# proto.net
KiCad netlist of a schematic drawn in EAGLE
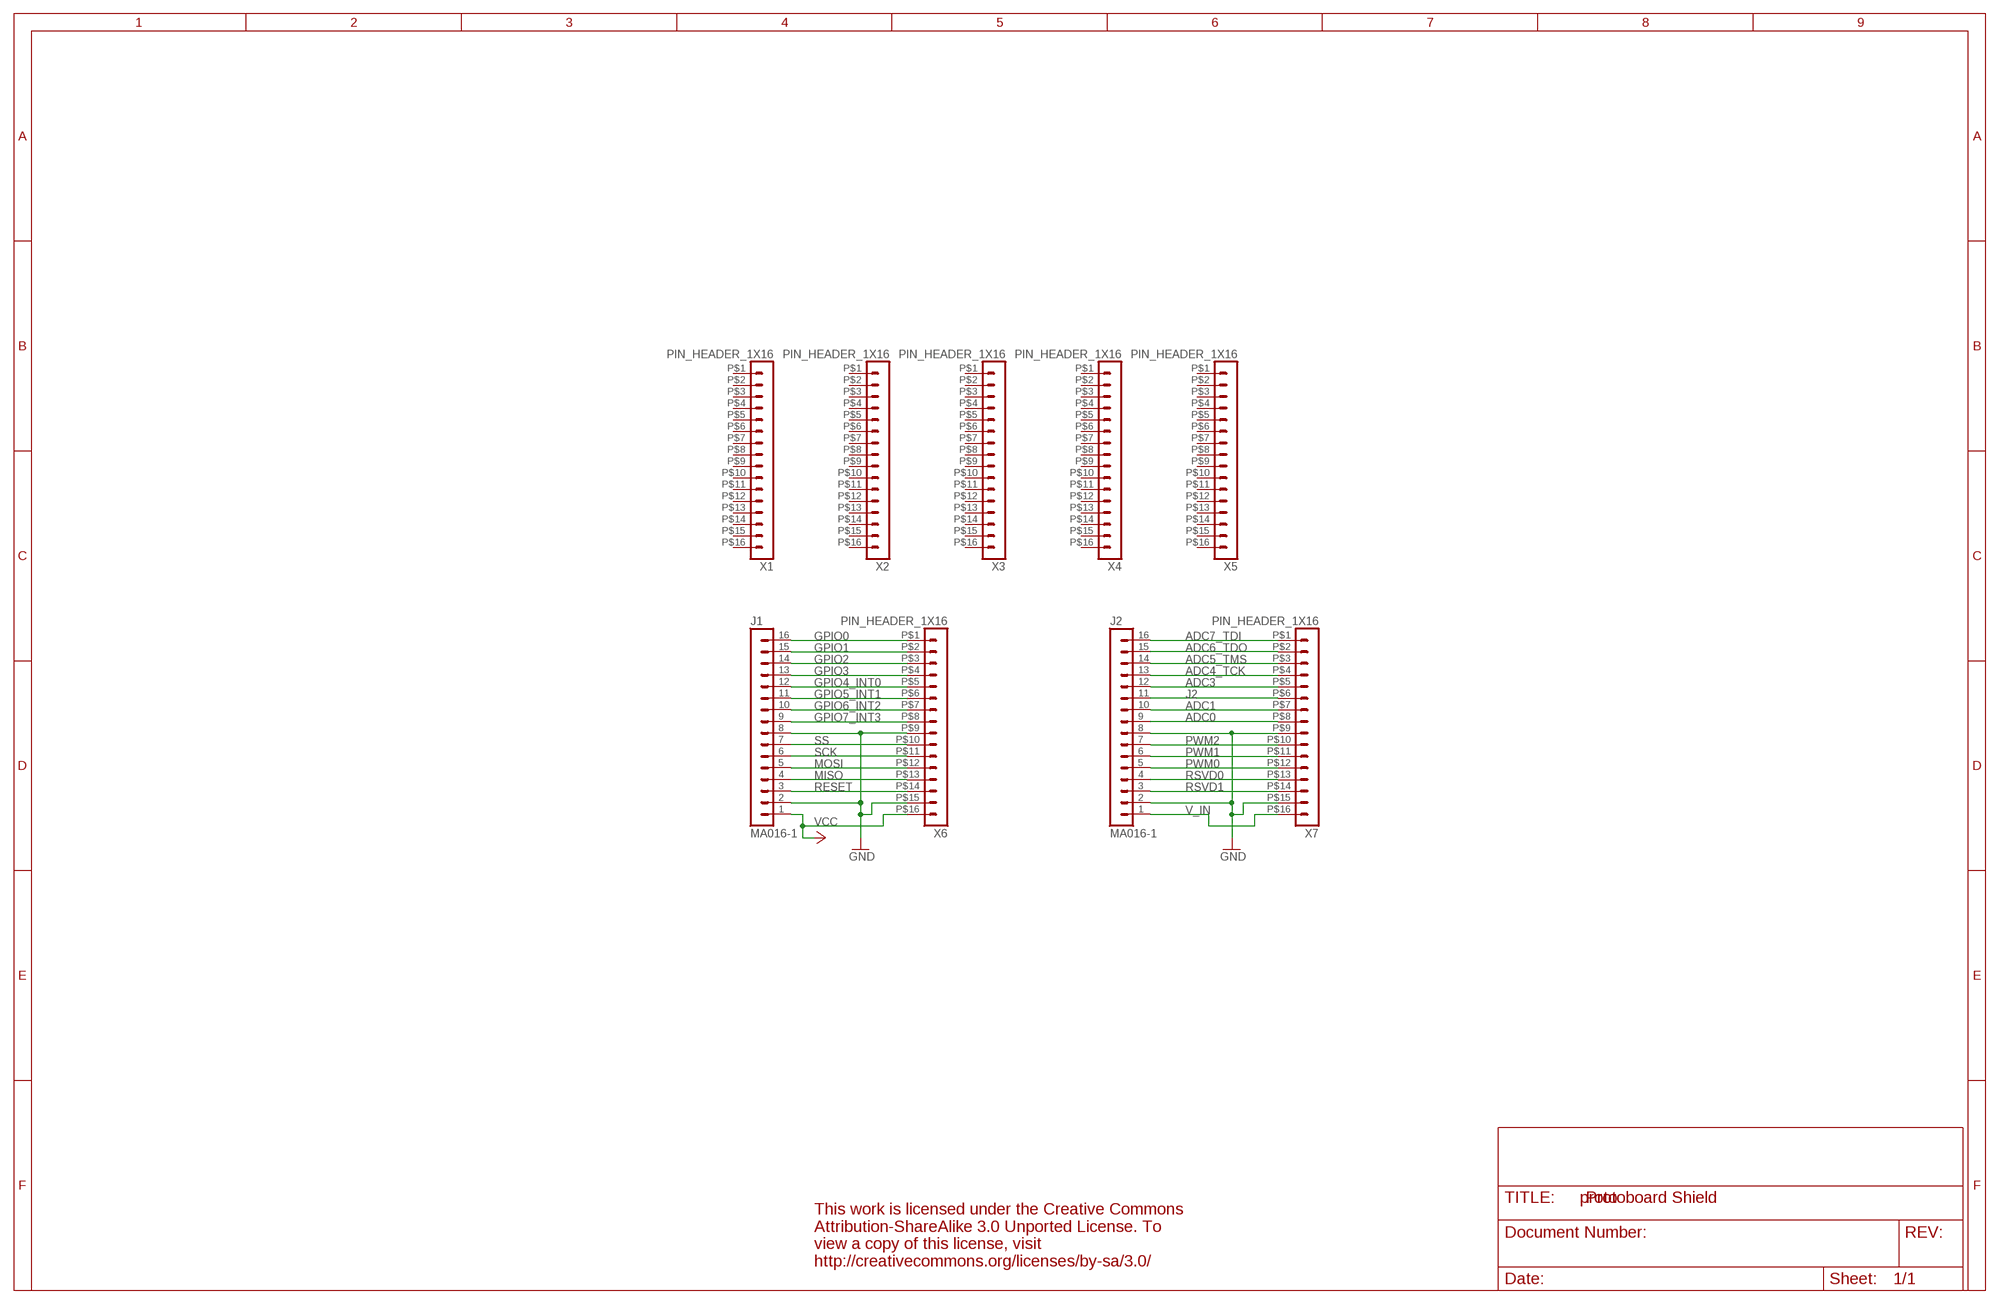
[diagram p0: schematic, sheet 1]

(export (version "E")
  (design (tool "Eeschema 10.0.6"))
  (components
    (comp (ref "J1")
      (value "MA016-1")
      (footprint "eagle-import:MA016-1")
      (libsource (lib "eagle-import") (part "MA016-1"))
    )
    (comp (ref "J2")
      (value "MA016-1")
      (footprint "eagle-import:MA016-1")
      (libsource (lib "eagle-import") (part "MA016-1"))
    )
    (comp (ref "X1")
      (value "PIN_HEADER_1X16")
      (footprint "eagle-import:PIN_HEADER_1X16")
      (libsource (lib "eagle-import") (part "PIN_HEADER_1X16"))
    )
    (comp (ref "X2")
      (value "PIN_HEADER_1X16")
      (footprint "eagle-import:PIN_HEADER_1X16")
      (libsource (lib "eagle-import") (part "PIN_HEADER_1X16"))
    )
    (comp (ref "X3")
      (value "PIN_HEADER_1X16")
      (footprint "eagle-import:PIN_HEADER_1X16")
      (libsource (lib "eagle-import") (part "PIN_HEADER_1X16"))
    )
    (comp (ref "X4")
      (value "PIN_HEADER_1X16")
      (footprint "eagle-import:PIN_HEADER_1X16")
      (libsource (lib "eagle-import") (part "PIN_HEADER_1X16"))
    )
    (comp (ref "X5")
      (value "PIN_HEADER_1X16")
      (footprint "eagle-import:PIN_HEADER_1X16")
      (libsource (lib "eagle-import") (part "PIN_HEADER_1X16"))
    )
    (comp (ref "X6")
      (value "PIN_HEADER_1X16")
      (footprint "eagle-import:PIN_HEADER_1X16")
      (libsource (lib "eagle-import") (part "PIN_HEADER_1X16"))
    )
    (comp (ref "X7")
      (value "PIN_HEADER_1X16")
      (footprint "eagle-import:PIN_HEADER_1X16")
      (libsource (lib "eagle-import") (part "PIN_HEADER_1X16"))
    )
  )
  (nets
    (net (code "1") (name "/ADC0") (class "Default")
      (node (ref "J2") (pin "9") (pinfunction "9_9") (pintype "passive"))
      (node (ref "X7") (pin "P$8") (pinfunction "8_P$8") (pintype "passive"))
    )
    (net (code "2") (name "/ADC1") (class "Default")
      (node (ref "J2") (pin "10") (pinfunction "10_10") (pintype "passive"))
      (node (ref "X7") (pin "P$7") (pinfunction "7_P$7") (pintype "passive"))
    )
    (net (code "3") (name "/ADC3") (class "Default")
      (node (ref "J2") (pin "12") (pinfunction "12_12") (pintype "passive"))
      (node (ref "X7") (pin "P$5") (pinfunction "5_P$5") (pintype "passive"))
    )
    (net (code "4") (name "/ADC4_TCK") (class "Default")
      (node (ref "J2") (pin "13") (pinfunction "13_13") (pintype "passive"))
      (node (ref "X7") (pin "P$4") (pinfunction "4_P$4") (pintype "passive"))
    )
    (net (code "5") (name "/ADC5_TMS") (class "Default")
      (node (ref "J2") (pin "14") (pinfunction "14_14") (pintype "passive"))
      (node (ref "X7") (pin "P$3") (pinfunction "3_P$3") (pintype "passive"))
    )
    (net (code "6") (name "/ADC6_TDO") (class "Default")
      (node (ref "J2") (pin "15") (pinfunction "15_15") (pintype "passive"))
      (node (ref "X7") (pin "P$2") (pinfunction "2_P$2") (pintype "passive"))
    )
    (net (code "7") (name "/ADC7_TDI") (class "Default")
      (node (ref "J2") (pin "16") (pinfunction "16_16") (pintype "passive"))
      (node (ref "X7") (pin "P$1") (pinfunction "1_P$1") (pintype "passive"))
    )
    (net (code "8") (name "/GPIO0") (class "Default")
      (node (ref "J1") (pin "16") (pinfunction "16_16") (pintype "passive"))
      (node (ref "X6") (pin "P$1") (pinfunction "1_P$1") (pintype "passive"))
    )
    (net (code "9") (name "/GPIO1") (class "Default")
      (node (ref "J1") (pin "15") (pinfunction "15_15") (pintype "passive"))
      (node (ref "X6") (pin "P$2") (pinfunction "2_P$2") (pintype "passive"))
    )
    (net (code "10") (name "/GPIO2") (class "Default")
      (node (ref "J1") (pin "14") (pinfunction "14_14") (pintype "passive"))
      (node (ref "X6") (pin "P$3") (pinfunction "3_P$3") (pintype "passive"))
    )
    (net (code "11") (name "/GPIO3") (class "Default")
      (node (ref "J1") (pin "13") (pinfunction "13_13") (pintype "passive"))
      (node (ref "X6") (pin "P$4") (pinfunction "4_P$4") (pintype "passive"))
    )
    (net (code "12") (name "/GPIO4_INT0") (class "Default")
      (node (ref "J1") (pin "12") (pinfunction "12_12") (pintype "passive"))
      (node (ref "X6") (pin "P$5") (pinfunction "5_P$5") (pintype "passive"))
    )
    (net (code "13") (name "/GPIO5_INT1") (class "Default")
      (node (ref "J1") (pin "11") (pinfunction "11_11") (pintype "passive"))
      (node (ref "X6") (pin "P$6") (pinfunction "6_P$6") (pintype "passive"))
    )
    (net (code "14") (name "/GPIO6_INT2") (class "Default")
      (node (ref "J1") (pin "10") (pinfunction "10_10") (pintype "passive"))
      (node (ref "X6") (pin "P$7") (pinfunction "7_P$7") (pintype "passive"))
    )
    (net (code "15") (name "/GPIO7_INT3") (class "Default")
      (node (ref "J1") (pin "9") (pinfunction "9_9") (pintype "passive"))
      (node (ref "X6") (pin "P$8") (pinfunction "8_P$8") (pintype "passive"))
    )
    (net (code "16") (name "/J2") (class "Default")
      (node (ref "J2") (pin "11") (pinfunction "11_11") (pintype "passive"))
      (node (ref "X7") (pin "P$6") (pinfunction "6_P$6") (pintype "passive"))
    )
    (net (code "17") (name "/MISO") (class "Default")
      (node (ref "J1") (pin "4") (pinfunction "4_4") (pintype "passive"))
      (node (ref "X6") (pin "P$13") (pinfunction "13_P$13") (pintype "passive"))
    )
    (net (code "18") (name "/MOSI") (class "Default")
      (node (ref "J1") (pin "5") (pinfunction "5_5") (pintype "passive"))
      (node (ref "X6") (pin "P$12") (pinfunction "12_P$12") (pintype "passive"))
    )
    (net (code "19") (name "/PWM0") (class "Default")
      (node (ref "J2") (pin "5") (pinfunction "5_5") (pintype "passive"))
      (node (ref "X7") (pin "P$12") (pinfunction "12_P$12") (pintype "passive"))
    )
    (net (code "20") (name "/PWM1") (class "Default")
      (node (ref "J2") (pin "6") (pinfunction "6_6") (pintype "passive"))
      (node (ref "X7") (pin "P$11") (pinfunction "11_P$11") (pintype "passive"))
    )
    (net (code "21") (name "/PWM2") (class "Default")
      (node (ref "J2") (pin "7") (pinfunction "7_7") (pintype "passive"))
      (node (ref "X7") (pin "P$10") (pinfunction "10_P$10") (pintype "passive"))
    )
    (net (code "22") (name "/RESET") (class "Default")
      (node (ref "J1") (pin "3") (pinfunction "3_3") (pintype "passive"))
      (node (ref "X6") (pin "P$14") (pinfunction "14_P$14") (pintype "passive"))
    )
    (net (code "23") (name "/RSVD0") (class "Default")
      (node (ref "J2") (pin "4") (pinfunction "4_4") (pintype "passive"))
      (node (ref "X7") (pin "P$13") (pinfunction "13_P$13") (pintype "passive"))
    )
    (net (code "24") (name "/RSVD1") (class "Default")
      (node (ref "J2") (pin "3") (pinfunction "3_3") (pintype "passive"))
      (node (ref "X7") (pin "P$14") (pinfunction "14_P$14") (pintype "passive"))
    )
    (net (code "25") (name "/SCK") (class "Default")
      (node (ref "J1") (pin "6") (pinfunction "6_6") (pintype "passive"))
      (node (ref "X6") (pin "P$11") (pinfunction "11_P$11") (pintype "passive"))
    )
    (net (code "26") (name "/SS") (class "Default")
      (node (ref "J1") (pin "7") (pinfunction "7_7") (pintype "passive"))
      (node (ref "X6") (pin "P$10") (pinfunction "10_P$10") (pintype "passive"))
    )
    (net (code "27") (name "/V_IN") (class "Default")
      (node (ref "J2") (pin "1") (pinfunction "1_1") (pintype "passive"))
      (node (ref "X7") (pin "P$16") (pinfunction "16_P$16") (pintype "passive"))
    )
    (net (code "28") (name "GND") (class "Default")
      (node (ref "J1") (pin "2") (pinfunction "2_2") (pintype "passive"))
      (node (ref "J1") (pin "8") (pinfunction "8_8") (pintype "passive"))
      (node (ref "J2") (pin "2") (pinfunction "2_2") (pintype "passive"))
      (node (ref "J2") (pin "8") (pinfunction "8_8") (pintype "passive"))
      (node (ref "X6") (pin "P$15") (pinfunction "15_P$15") (pintype "passive"))
      (node (ref "X6") (pin "P$9") (pinfunction "9_P$9") (pintype "passive"))
      (node (ref "X7") (pin "P$15") (pinfunction "15_P$15") (pintype "passive"))
      (node (ref "X7") (pin "P$9") (pinfunction "9_P$9") (pintype "passive"))
    )
    (net (code "29") (name "VCC") (class "Default")
      (node (ref "J1") (pin "1") (pinfunction "1_1") (pintype "passive"))
      (node (ref "X6") (pin "P$16") (pinfunction "16_P$16") (pintype "passive"))
    )
    (net (code "30") (name "unconnected-(X1-1-PadP$1)") (class "Default")
      (node (ref "X1") (pin "P$1") (pinfunction "1_P$1") (pintype "passive"))
    )
    (net (code "31") (name "unconnected-(X1-2-PadP$2)") (class "Default")
      (node (ref "X1") (pin "P$2") (pinfunction "2_P$2") (pintype "passive"))
    )
    (net (code "32") (name "unconnected-(X1-3-PadP$3)") (class "Default")
      (node (ref "X1") (pin "P$3") (pinfunction "3_P$3") (pintype "passive"))
    )
    (net (code "33") (name "unconnected-(X1-4-PadP$4)") (class "Default")
      (node (ref "X1") (pin "P$4") (pinfunction "4_P$4") (pintype "passive"))
    )
    (net (code "34") (name "unconnected-(X1-5-PadP$5)") (class "Default")
      (node (ref "X1") (pin "P$5") (pinfunction "5_P$5") (pintype "passive"))
    )
    (net (code "35") (name "unconnected-(X1-6-PadP$6)") (class "Default")
      (node (ref "X1") (pin "P$6") (pinfunction "6_P$6") (pintype "passive"))
    )
    (net (code "36") (name "unconnected-(X1-7-PadP$7)") (class "Default")
      (node (ref "X1") (pin "P$7") (pinfunction "7_P$7") (pintype "passive"))
    )
    (net (code "37") (name "unconnected-(X1-8-PadP$8)") (class "Default")
      (node (ref "X1") (pin "P$8") (pinfunction "8_P$8") (pintype "passive"))
    )
    (net (code "38") (name "unconnected-(X1-9-PadP$9)") (class "Default")
      (node (ref "X1") (pin "P$9") (pinfunction "9_P$9") (pintype "passive"))
    )
    (net (code "39") (name "unconnected-(X1-10-PadP$10)") (class "Default")
      (node (ref "X1") (pin "P$10") (pinfunction "10_P$10") (pintype "passive"))
    )
    (net (code "40") (name "unconnected-(X1-11-PadP$11)") (class "Default")
      (node (ref "X1") (pin "P$11") (pinfunction "11_P$11") (pintype "passive"))
    )
    (net (code "41") (name "unconnected-(X1-12-PadP$12)") (class "Default")
      (node (ref "X1") (pin "P$12") (pinfunction "12_P$12") (pintype "passive"))
    )
    (net (code "42") (name "unconnected-(X1-13-PadP$13)") (class "Default")
      (node (ref "X1") (pin "P$13") (pinfunction "13_P$13") (pintype "passive"))
    )
    (net (code "43") (name "unconnected-(X1-14-PadP$14)") (class "Default")
      (node (ref "X1") (pin "P$14") (pinfunction "14_P$14") (pintype "passive"))
    )
    (net (code "44") (name "unconnected-(X1-15-PadP$15)") (class "Default")
      (node (ref "X1") (pin "P$15") (pinfunction "15_P$15") (pintype "passive"))
    )
    (net (code "45") (name "unconnected-(X1-16-PadP$16)") (class "Default")
      (node (ref "X1") (pin "P$16") (pinfunction "16_P$16") (pintype "passive"))
    )
    (net (code "46") (name "unconnected-(X2-1-PadP$1)") (class "Default")
      (node (ref "X2") (pin "P$1") (pinfunction "1_P$1") (pintype "passive"))
    )
    (net (code "47") (name "unconnected-(X2-2-PadP$2)") (class "Default")
      (node (ref "X2") (pin "P$2") (pinfunction "2_P$2") (pintype "passive"))
    )
    (net (code "48") (name "unconnected-(X2-3-PadP$3)") (class "Default")
      (node (ref "X2") (pin "P$3") (pinfunction "3_P$3") (pintype "passive"))
    )
    (net (code "49") (name "unconnected-(X2-4-PadP$4)") (class "Default")
      (node (ref "X2") (pin "P$4") (pinfunction "4_P$4") (pintype "passive"))
    )
    (net (code "50") (name "unconnected-(X2-5-PadP$5)") (class "Default")
      (node (ref "X2") (pin "P$5") (pinfunction "5_P$5") (pintype "passive"))
    )
    (net (code "51") (name "unconnected-(X2-6-PadP$6)") (class "Default")
      (node (ref "X2") (pin "P$6") (pinfunction "6_P$6") (pintype "passive"))
    )
    (net (code "52") (name "unconnected-(X2-7-PadP$7)") (class "Default")
      (node (ref "X2") (pin "P$7") (pinfunction "7_P$7") (pintype "passive"))
    )
    (net (code "53") (name "unconnected-(X2-8-PadP$8)") (class "Default")
      (node (ref "X2") (pin "P$8") (pinfunction "8_P$8") (pintype "passive"))
    )
    (net (code "54") (name "unconnected-(X2-9-PadP$9)") (class "Default")
      (node (ref "X2") (pin "P$9") (pinfunction "9_P$9") (pintype "passive"))
    )
    (net (code "55") (name "unconnected-(X2-10-PadP$10)") (class "Default")
      (node (ref "X2") (pin "P$10") (pinfunction "10_P$10") (pintype "passive"))
    )
    (net (code "56") (name "unconnected-(X2-11-PadP$11)") (class "Default")
      (node (ref "X2") (pin "P$11") (pinfunction "11_P$11") (pintype "passive"))
    )
    (net (code "57") (name "unconnected-(X2-12-PadP$12)") (class "Default")
      (node (ref "X2") (pin "P$12") (pinfunction "12_P$12") (pintype "passive"))
    )
    (net (code "58") (name "unconnected-(X2-13-PadP$13)") (class "Default")
      (node (ref "X2") (pin "P$13") (pinfunction "13_P$13") (pintype "passive"))
    )
    (net (code "59") (name "unconnected-(X2-14-PadP$14)") (class "Default")
      (node (ref "X2") (pin "P$14") (pinfunction "14_P$14") (pintype "passive"))
    )
    (net (code "60") (name "unconnected-(X2-15-PadP$15)") (class "Default")
      (node (ref "X2") (pin "P$15") (pinfunction "15_P$15") (pintype "passive"))
    )
    (net (code "61") (name "unconnected-(X2-16-PadP$16)") (class "Default")
      (node (ref "X2") (pin "P$16") (pinfunction "16_P$16") (pintype "passive"))
    )
    (net (code "62") (name "unconnected-(X3-1-PadP$1)") (class "Default")
      (node (ref "X3") (pin "P$1") (pinfunction "1_P$1") (pintype "passive"))
    )
    (net (code "63") (name "unconnected-(X3-2-PadP$2)") (class "Default")
      (node (ref "X3") (pin "P$2") (pinfunction "2_P$2") (pintype "passive"))
    )
    (net (code "64") (name "unconnected-(X3-3-PadP$3)") (class "Default")
      (node (ref "X3") (pin "P$3") (pinfunction "3_P$3") (pintype "passive"))
    )
    (net (code "65") (name "unconnected-(X3-4-PadP$4)") (class "Default")
      (node (ref "X3") (pin "P$4") (pinfunction "4_P$4") (pintype "passive"))
    )
    (net (code "66") (name "unconnected-(X3-5-PadP$5)") (class "Default")
      (node (ref "X3") (pin "P$5") (pinfunction "5_P$5") (pintype "passive"))
    )
    (net (code "67") (name "unconnected-(X3-6-PadP$6)") (class "Default")
      (node (ref "X3") (pin "P$6") (pinfunction "6_P$6") (pintype "passive"))
    )
    (net (code "68") (name "unconnected-(X3-7-PadP$7)") (class "Default")
      (node (ref "X3") (pin "P$7") (pinfunction "7_P$7") (pintype "passive"))
    )
    (net (code "69") (name "unconnected-(X3-8-PadP$8)") (class "Default")
      (node (ref "X3") (pin "P$8") (pinfunction "8_P$8") (pintype "passive"))
    )
    (net (code "70") (name "unconnected-(X3-9-PadP$9)") (class "Default")
      (node (ref "X3") (pin "P$9") (pinfunction "9_P$9") (pintype "passive"))
    )
    (net (code "71") (name "unconnected-(X3-10-PadP$10)") (class "Default")
      (node (ref "X3") (pin "P$10") (pinfunction "10_P$10") (pintype "passive"))
    )
    (net (code "72") (name "unconnected-(X3-11-PadP$11)") (class "Default")
      (node (ref "X3") (pin "P$11") (pinfunction "11_P$11") (pintype "passive"))
    )
    (net (code "73") (name "unconnected-(X3-12-PadP$12)") (class "Default")
      (node (ref "X3") (pin "P$12") (pinfunction "12_P$12") (pintype "passive"))
    )
    (net (code "74") (name "unconnected-(X3-13-PadP$13)") (class "Default")
      (node (ref "X3") (pin "P$13") (pinfunction "13_P$13") (pintype "passive"))
    )
    (net (code "75") (name "unconnected-(X3-14-PadP$14)") (class "Default")
      (node (ref "X3") (pin "P$14") (pinfunction "14_P$14") (pintype "passive"))
    )
    (net (code "76") (name "unconnected-(X3-15-PadP$15)") (class "Default")
      (node (ref "X3") (pin "P$15") (pinfunction "15_P$15") (pintype "passive"))
    )
    (net (code "77") (name "unconnected-(X3-16-PadP$16)") (class "Default")
      (node (ref "X3") (pin "P$16") (pinfunction "16_P$16") (pintype "passive"))
    )
    (net (code "78") (name "unconnected-(X4-1-PadP$1)") (class "Default")
      (node (ref "X4") (pin "P$1") (pinfunction "1_P$1") (pintype "passive"))
    )
    (net (code "79") (name "unconnected-(X4-2-PadP$2)") (class "Default")
      (node (ref "X4") (pin "P$2") (pinfunction "2_P$2") (pintype "passive"))
    )
    (net (code "80") (name "unconnected-(X4-3-PadP$3)") (class "Default")
      (node (ref "X4") (pin "P$3") (pinfunction "3_P$3") (pintype "passive"))
    )
    (net (code "81") (name "unconnected-(X4-4-PadP$4)") (class "Default")
      (node (ref "X4") (pin "P$4") (pinfunction "4_P$4") (pintype "passive"))
    )
    (net (code "82") (name "unconnected-(X4-5-PadP$5)") (class "Default")
      (node (ref "X4") (pin "P$5") (pinfunction "5_P$5") (pintype "passive"))
    )
    (net (code "83") (name "unconnected-(X4-6-PadP$6)") (class "Default")
      (node (ref "X4") (pin "P$6") (pinfunction "6_P$6") (pintype "passive"))
    )
    (net (code "84") (name "unconnected-(X4-7-PadP$7)") (class "Default")
      (node (ref "X4") (pin "P$7") (pinfunction "7_P$7") (pintype "passive"))
    )
    (net (code "85") (name "unconnected-(X4-8-PadP$8)") (class "Default")
      (node (ref "X4") (pin "P$8") (pinfunction "8_P$8") (pintype "passive"))
    )
    (net (code "86") (name "unconnected-(X4-9-PadP$9)") (class "Default")
      (node (ref "X4") (pin "P$9") (pinfunction "9_P$9") (pintype "passive"))
    )
    (net (code "87") (name "unconnected-(X4-10-PadP$10)") (class "Default")
      (node (ref "X4") (pin "P$10") (pinfunction "10_P$10") (pintype "passive"))
    )
    (net (code "88") (name "unconnected-(X4-11-PadP$11)") (class "Default")
      (node (ref "X4") (pin "P$11") (pinfunction "11_P$11") (pintype "passive"))
    )
    (net (code "89") (name "unconnected-(X4-12-PadP$12)") (class "Default")
      (node (ref "X4") (pin "P$12") (pinfunction "12_P$12") (pintype "passive"))
    )
    (net (code "90") (name "unconnected-(X4-13-PadP$13)") (class "Default")
      (node (ref "X4") (pin "P$13") (pinfunction "13_P$13") (pintype "passive"))
    )
    (net (code "91") (name "unconnected-(X4-14-PadP$14)") (class "Default")
      (node (ref "X4") (pin "P$14") (pinfunction "14_P$14") (pintype "passive"))
    )
    (net (code "92") (name "unconnected-(X4-15-PadP$15)") (class "Default")
      (node (ref "X4") (pin "P$15") (pinfunction "15_P$15") (pintype "passive"))
    )
    (net (code "93") (name "unconnected-(X4-16-PadP$16)") (class "Default")
      (node (ref "X4") (pin "P$16") (pinfunction "16_P$16") (pintype "passive"))
    )
    (net (code "94") (name "unconnected-(X5-1-PadP$1)") (class "Default")
      (node (ref "X5") (pin "P$1") (pinfunction "1_P$1") (pintype "passive"))
    )
    (net (code "95") (name "unconnected-(X5-2-PadP$2)") (class "Default")
      (node (ref "X5") (pin "P$2") (pinfunction "2_P$2") (pintype "passive"))
    )
    (net (code "96") (name "unconnected-(X5-3-PadP$3)") (class "Default")
      (node (ref "X5") (pin "P$3") (pinfunction "3_P$3") (pintype "passive"))
    )
    (net (code "97") (name "unconnected-(X5-4-PadP$4)") (class "Default")
      (node (ref "X5") (pin "P$4") (pinfunction "4_P$4") (pintype "passive"))
    )
    (net (code "98") (name "unconnected-(X5-5-PadP$5)") (class "Default")
      (node (ref "X5") (pin "P$5") (pinfunction "5_P$5") (pintype "passive"))
    )
    (net (code "99") (name "unconnected-(X5-6-PadP$6)") (class "Default")
      (node (ref "X5") (pin "P$6") (pinfunction "6_P$6") (pintype "passive"))
    )
    (net (code "100") (name "unconnected-(X5-7-PadP$7)") (class "Default")
      (node (ref "X5") (pin "P$7") (pinfunction "7_P$7") (pintype "passive"))
    )
    (net (code "101") (name "unconnected-(X5-8-PadP$8)") (class "Default")
      (node (ref "X5") (pin "P$8") (pinfunction "8_P$8") (pintype "passive"))
    )
    (net (code "102") (name "unconnected-(X5-9-PadP$9)") (class "Default")
      (node (ref "X5") (pin "P$9") (pinfunction "9_P$9") (pintype "passive"))
    )
    (net (code "103") (name "unconnected-(X5-10-PadP$10)") (class "Default")
      (node (ref "X5") (pin "P$10") (pinfunction "10_P$10") (pintype "passive"))
    )
    (net (code "104") (name "unconnected-(X5-11-PadP$11)") (class "Default")
      (node (ref "X5") (pin "P$11") (pinfunction "11_P$11") (pintype "passive"))
    )
    (net (code "105") (name "unconnected-(X5-12-PadP$12)") (class "Default")
      (node (ref "X5") (pin "P$12") (pinfunction "12_P$12") (pintype "passive"))
    )
    (net (code "106") (name "unconnected-(X5-13-PadP$13)") (class "Default")
      (node (ref "X5") (pin "P$13") (pinfunction "13_P$13") (pintype "passive"))
    )
    (net (code "107") (name "unconnected-(X5-14-PadP$14)") (class "Default")
      (node (ref "X5") (pin "P$14") (pinfunction "14_P$14") (pintype "passive"))
    )
    (net (code "108") (name "unconnected-(X5-15-PadP$15)") (class "Default")
      (node (ref "X5") (pin "P$15") (pinfunction "15_P$15") (pintype "passive"))
    )
    (net (code "109") (name "unconnected-(X5-16-PadP$16)") (class "Default")
      (node (ref "X5") (pin "P$16") (pinfunction "16_P$16") (pintype "passive"))
    )
  )
)
